# header_conn.net
KiCad netlist of a schematic drawn in Altium Designer
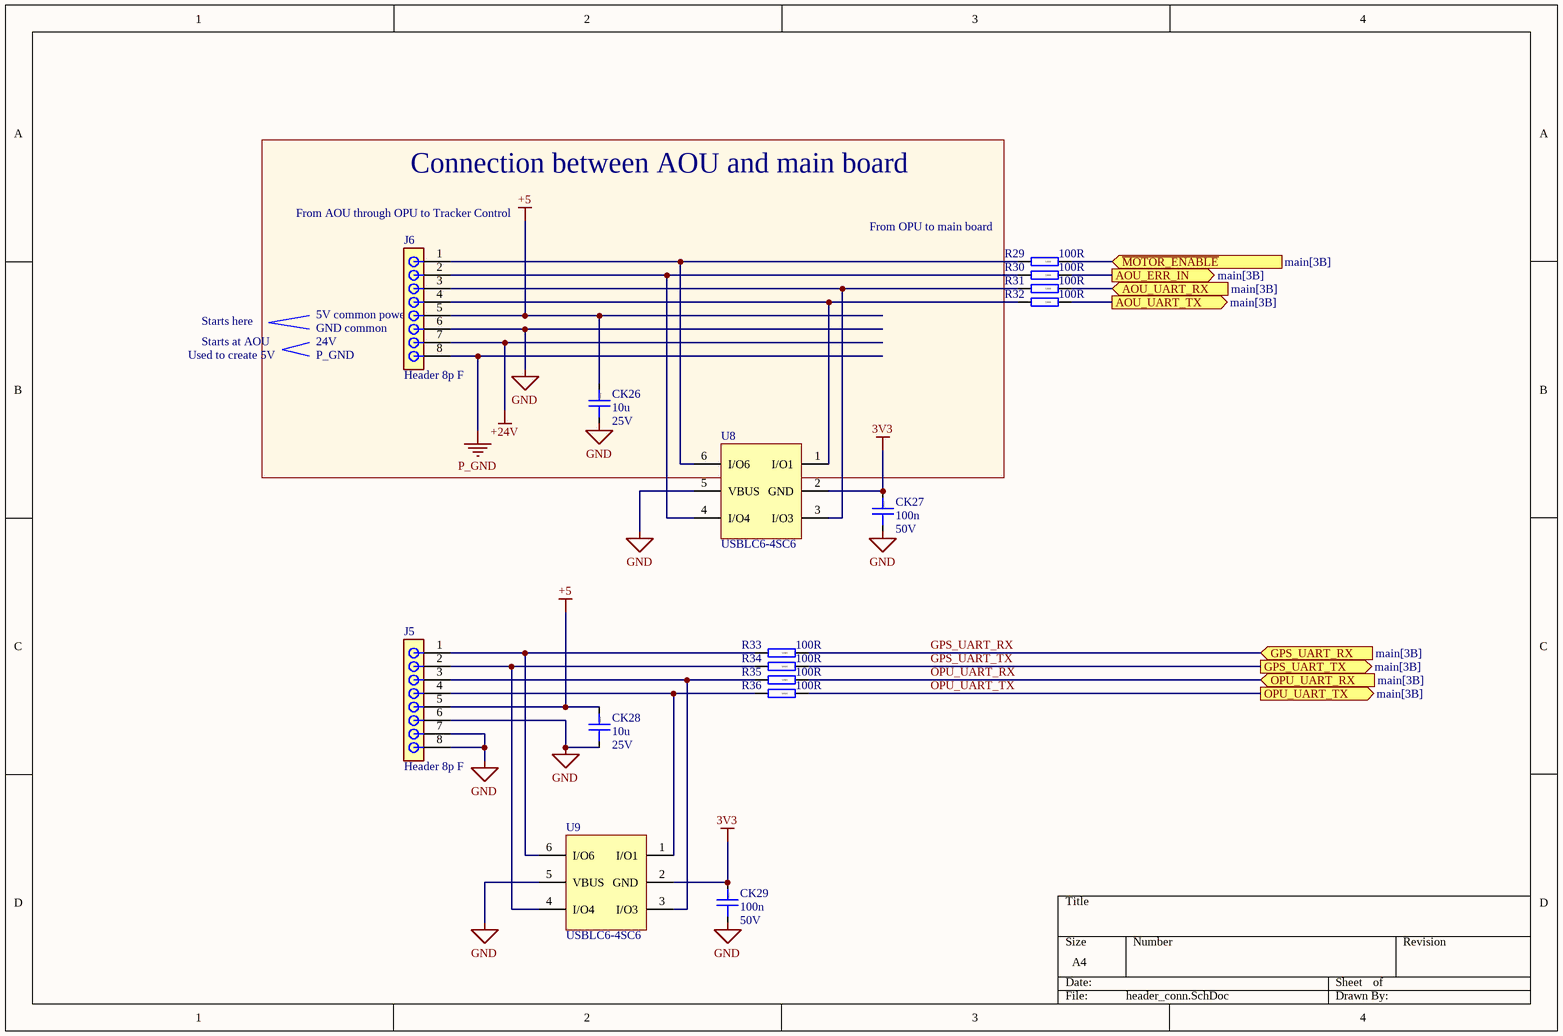
[diagram p0: header_conn.SchDoc]

(export (version "E")
  (design (tool "Eeschema 10.0.6"))
  (components
    (comp (ref "CK26")
      (value "10u")
      (footprint "CAP0805")
      (description "25V 10uF X5R ±10% 0805 Multilayer Ceramic Capacitors MLCC - SMD/SMT ROHS")
      (fields (field (name "JLCPCB PART") "C15850") (field (name "VOLTAGE RATING") "25V"))
      (libsource (lib "Kubikova ultra knihovna") (part "Cap 10u 0805"))
    )
    (comp (ref "CK27")
      (value "100n")
      (footprint "CAP0603")
      (description "50V 100nF X7R ±10% 0603 Multilayer Ceramic Capacitors MLCC - SMD/SMT ROHS")
      (fields (field (name "JLCPCB PART") "C14663") (field (name "VOLTAGE RATING") "50V"))
      (libsource (lib "Kubikova ultra knihovna") (part "Cap 100n 0603"))
    )
    (comp (ref "CK28")
      (value "10u")
      (footprint "CAP0805")
      (description "25V 10uF X5R ±10% 0805 Multilayer Ceramic Capacitors MLCC - SMD/SMT ROHS")
      (fields (field (name "JLCPCB PART") "C15850") (field (name "VOLTAGE RATING") "25V"))
      (libsource (lib "Kubikova ultra knihovna") (part "Cap 10u 0805"))
    )
    (comp (ref "CK29")
      (value "100n")
      (footprint "CAP0603")
      (description "50V 100nF X7R ±10% 0603 Multilayer Ceramic Capacitors MLCC - SMD/SMT ROHS")
      (fields (field (name "JLCPCB PART") "C14663") (field (name "VOLTAGE RATING") "50V"))
      (libsource (lib "Kubikova ultra knihovna") (part "Cap 100n 0603"))
    )
    (comp (ref "J5")
      (value "Header 8p F")
      (footprint "Pin header 8p - F")
      (fields (field (name "MANUFACTURER_PART_NUMBER") "DS1021-1*2SF11-B"))
      (libsource (lib "Kubikova ultra knihovna") (part "Pin header 8p_F"))
    )
    (comp (ref "J6")
      (value "Header 8p F")
      (footprint "Pin header 8p - F")
      (fields (field (name "MANUFACTURER_PART_NUMBER") "DS1021-1*2SF11-B"))
      (libsource (lib "Kubikova ultra knihovna") (part "Pin header 8p_F"))
    )
    (comp (ref "R29")
      (value "100R")
      (footprint "RESC2012X06N(SMR0805)")
      (description "125mW Thick Film Resistors 150V ±100ppm/℃ ±1% 100Ω 0805 Chip Resistor - Surface Mount ROHS")
      (fields (field (name "JLCPCB PART") "C17408") (field (name "AUTHOR") "JP/27.03.2014"))
      (libsource (lib "Kubikova ultra knihovna") (part "Res 100R 0805"))
    )
    (comp (ref "R30")
      (value "100R")
      (footprint "RESC2012X06N(SMR0805)")
      (description "125mW Thick Film Resistors 150V ±100ppm/℃ ±1% 100Ω 0805 Chip Resistor - Surface Mount ROHS")
      (fields (field (name "JLCPCB PART") "C17408") (field (name "AUTHOR") "JP/27.03.2014"))
      (libsource (lib "Kubikova ultra knihovna") (part "Res 100R 0805"))
    )
    (comp (ref "R31")
      (value "100R")
      (footprint "RESC2012X06N(SMR0805)")
      (description "125mW Thick Film Resistors 150V ±100ppm/℃ ±1% 100Ω 0805 Chip Resistor - Surface Mount ROHS")
      (fields (field (name "JLCPCB PART") "C17408") (field (name "AUTHOR") "JP/27.03.2014"))
      (libsource (lib "Kubikova ultra knihovna") (part "Res 100R 0805"))
    )
    (comp (ref "R32")
      (value "100R")
      (footprint "RESC2012X06N(SMR0805)")
      (description "125mW Thick Film Resistors 150V ±100ppm/℃ ±1% 100Ω 0805 Chip Resistor - Surface Mount ROHS")
      (fields (field (name "JLCPCB PART") "C17408") (field (name "AUTHOR") "JP/27.03.2014"))
      (libsource (lib "Kubikova ultra knihovna") (part "Res 100R 0805"))
    )
    (comp (ref "R33")
      (value "100R")
      (footprint "RESC2012X06N(SMR0805)")
      (description "125mW Thick Film Resistors 150V ±100ppm/℃ ±1% 100Ω 0805 Chip Resistor - Surface Mount ROHS")
      (fields (field (name "JLCPCB PART") "C17408") (field (name "AUTHOR") "JP/27.03.2014"))
      (libsource (lib "Kubikova ultra knihovna") (part "Res 100R 0805"))
    )
    (comp (ref "R34")
      (value "100R")
      (footprint "RESC2012X06N(SMR0805)")
      (description "125mW Thick Film Resistors 150V ±100ppm/℃ ±1% 100Ω 0805 Chip Resistor - Surface Mount ROHS")
      (fields (field (name "JLCPCB PART") "C17408") (field (name "AUTHOR") "JP/27.03.2014"))
      (libsource (lib "Kubikova ultra knihovna") (part "Res 100R 0805"))
    )
    (comp (ref "R35")
      (value "100R")
      (footprint "RESC2012X06N(SMR0805)")
      (description "125mW Thick Film Resistors 150V ±100ppm/℃ ±1% 100Ω 0805 Chip Resistor - Surface Mount ROHS")
      (fields (field (name "JLCPCB PART") "C17408") (field (name "AUTHOR") "JP/27.03.2014"))
      (libsource (lib "Kubikova ultra knihovna") (part "Res 100R 0805"))
    )
    (comp (ref "R36")
      (value "100R")
      (footprint "RESC2012X06N(SMR0805)")
      (description "125mW Thick Film Resistors 150V ±100ppm/℃ ±1% 100Ω 0805 Chip Resistor - Surface Mount ROHS")
      (fields (field (name "JLCPCB PART") "C17408") (field (name "AUTHOR") "JP/27.03.2014"))
      (libsource (lib "Kubikova ultra knihovna") (part "Res 100R 0805"))
    )
    (comp (ref "U8")
      (value "USBLC6-4SC6")
      (footprint "SOT23-6")
      (description "5A 17V 6V Unidirectional 5.25V SOT-23-6 ESD and Surge Protection (TVS/ESD) ROHS")
      (fields (field (name "JLCPCB PART") "C111212"))
      (libsource (lib "Kubikova ultra knihovna") (part "USBLC6-4SC6"))
    )
    (comp (ref "U9")
      (value "USBLC6-4SC6")
      (footprint "SOT23-6")
      (description "5A 17V 6V Unidirectional 5.25V SOT-23-6 ESD and Surge Protection (TVS/ESD) ROHS")
      (fields (field (name "JLCPCB PART") "C111212"))
      (libsource (lib "Kubikova ultra knihovna") (part "USBLC6-4SC6"))
    )
  )
  (nets
    (net (code "1") (name "+5") (class "Default")
      (node (ref "CK26") (pin "1") (pinfunction "1_1") (pintype "passive"))
      (node (ref "CK28") (pin "1") (pinfunction "1_1") (pintype "passive"))
      (node (ref "J5") (pin "5") (pinfunction "5_5") (pintype "passive"))
      (node (ref "J6") (pin "5") (pinfunction "5_5") (pintype "passive"))
    )
    (net (code "2") (name "+24V") (class "Default")
      (node (ref "J6") (pin "7") (pinfunction "7_7") (pintype "passive"))
    )
    (net (code "3") (name "/AOU_ERR_IN") (class "Default")
      (node (ref "R30") (pin "2") (pinfunction "2_2") (pintype "passive"))
    )
    (net (code "4") (name "/AOU_UART_RX") (class "Default")
      (node (ref "R31") (pin "2") (pinfunction "2_2") (pintype "passive"))
    )
    (net (code "5") (name "/AOU_UART_TX") (class "Default")
      (node (ref "R32") (pin "2") (pinfunction "2_2") (pintype "passive"))
    )
    (net (code "6") (name "/GPS_UART_RX") (class "Default")
      (node (ref "R33") (pin "2") (pinfunction "2_2") (pintype "passive"))
    )
    (net (code "7") (name "/GPS_UART_TX") (class "Default")
      (node (ref "R34") (pin "2") (pinfunction "2_2") (pintype "passive"))
    )
    (net (code "8") (name "/OPU_UART_RX") (class "Default")
      (node (ref "R35") (pin "2") (pinfunction "2_2") (pintype "passive"))
    )
    (net (code "9") (name "/OPU_UART_TX") (class "Default")
      (node (ref "R36") (pin "2") (pinfunction "2_2") (pintype "passive"))
    )
    (net (code "10") (name "/~{MOTOR_ENABLE}") (class "Default")
      (node (ref "R29") (pin "2") (pinfunction "2_2") (pintype "passive"))
    )
    (net (code "11") (name "3V3") (class "Default")
      (node (ref "CK27") (pin "1") (pinfunction "1_1") (pintype "passive"))
      (node (ref "CK29") (pin "1") (pinfunction "1_1") (pintype "passive"))
      (node (ref "U8") (pin "2") (pinfunction "GND_2") (pintype "passive"))
      (node (ref "U9") (pin "2") (pinfunction "GND_2") (pintype "passive"))
    )
    (net (code "12") (name "GND") (class "Default")
      (node (ref "CK26") (pin "2") (pinfunction "2_2") (pintype "passive"))
      (node (ref "CK27") (pin "2") (pinfunction "2_2") (pintype "passive"))
      (node (ref "CK28") (pin "2") (pinfunction "2_2") (pintype "passive"))
      (node (ref "CK29") (pin "2") (pinfunction "2_2") (pintype "passive"))
      (node (ref "J5") (pin "6") (pinfunction "6_6") (pintype "passive"))
      (node (ref "J5") (pin "7") (pinfunction "7_7") (pintype "passive"))
      (node (ref "J5") (pin "8") (pinfunction "8_8") (pintype "passive"))
      (node (ref "J6") (pin "6") (pinfunction "6_6") (pintype "passive"))
      (node (ref "U8") (pin "5") (pinfunction "VBUS_5") (pintype "passive"))
      (node (ref "U9") (pin "5") (pinfunction "VBUS_5") (pintype "passive"))
    )
    (net (code "13") (name "Net-(U8-I{slash}O1)") (class "Default")
      (node (ref "J6") (pin "4") (pinfunction "4_4") (pintype "passive"))
      (node (ref "R32") (pin "1") (pinfunction "1_1") (pintype "passive"))
      (node (ref "U8") (pin "1") (pinfunction "I/O1_1") (pintype "passive"))
    )
    (net (code "14") (name "Net-(U8-I{slash}O3)") (class "Default")
      (node (ref "J6") (pin "3") (pinfunction "3_3") (pintype "passive"))
      (node (ref "R31") (pin "1") (pinfunction "1_1") (pintype "passive"))
      (node (ref "U8") (pin "3") (pinfunction "I/O3_3") (pintype "passive"))
    )
    (net (code "15") (name "Net-(U8-I{slash}O4)") (class "Default")
      (node (ref "J6") (pin "2") (pinfunction "2_2") (pintype "passive"))
      (node (ref "R30") (pin "1") (pinfunction "1_1") (pintype "passive"))
      (node (ref "U8") (pin "4") (pinfunction "I/O4_4") (pintype "passive"))
    )
    (net (code "16") (name "Net-(U8-I{slash}O6)") (class "Default")
      (node (ref "J6") (pin "1") (pinfunction "1_1") (pintype "passive"))
      (node (ref "R29") (pin "1") (pinfunction "1_1") (pintype "passive"))
      (node (ref "U8") (pin "6") (pinfunction "I/O6_6") (pintype "passive"))
    )
    (net (code "17") (name "Net-(U9-I{slash}O1)") (class "Default")
      (node (ref "J5") (pin "4") (pinfunction "4_4") (pintype "passive"))
      (node (ref "R36") (pin "1") (pinfunction "1_1") (pintype "passive"))
      (node (ref "U9") (pin "1") (pinfunction "I/O1_1") (pintype "passive"))
    )
    (net (code "18") (name "Net-(U9-I{slash}O3)") (class "Default")
      (node (ref "J5") (pin "3") (pinfunction "3_3") (pintype "passive"))
      (node (ref "R35") (pin "1") (pinfunction "1_1") (pintype "passive"))
      (node (ref "U9") (pin "3") (pinfunction "I/O3_3") (pintype "passive"))
    )
    (net (code "19") (name "Net-(U9-I{slash}O4)") (class "Default")
      (node (ref "J5") (pin "2") (pinfunction "2_2") (pintype "passive"))
      (node (ref "R34") (pin "1") (pinfunction "1_1") (pintype "passive"))
      (node (ref "U9") (pin "4") (pinfunction "I/O4_4") (pintype "passive"))
    )
    (net (code "20") (name "Net-(U9-I{slash}O6)") (class "Default")
      (node (ref "J5") (pin "1") (pinfunction "1_1") (pintype "passive"))
      (node (ref "R33") (pin "1") (pinfunction "1_1") (pintype "passive"))
      (node (ref "U9") (pin "6") (pinfunction "I/O6_6") (pintype "passive"))
    )
    (net (code "21") (name "P_GND") (class "Default")
      (node (ref "J6") (pin "8") (pinfunction "8_8") (pintype "passive"))
    )
  )
)
